# schematic_sheet2.net
KiCad netlist of a schematic drawn in Altium Designer
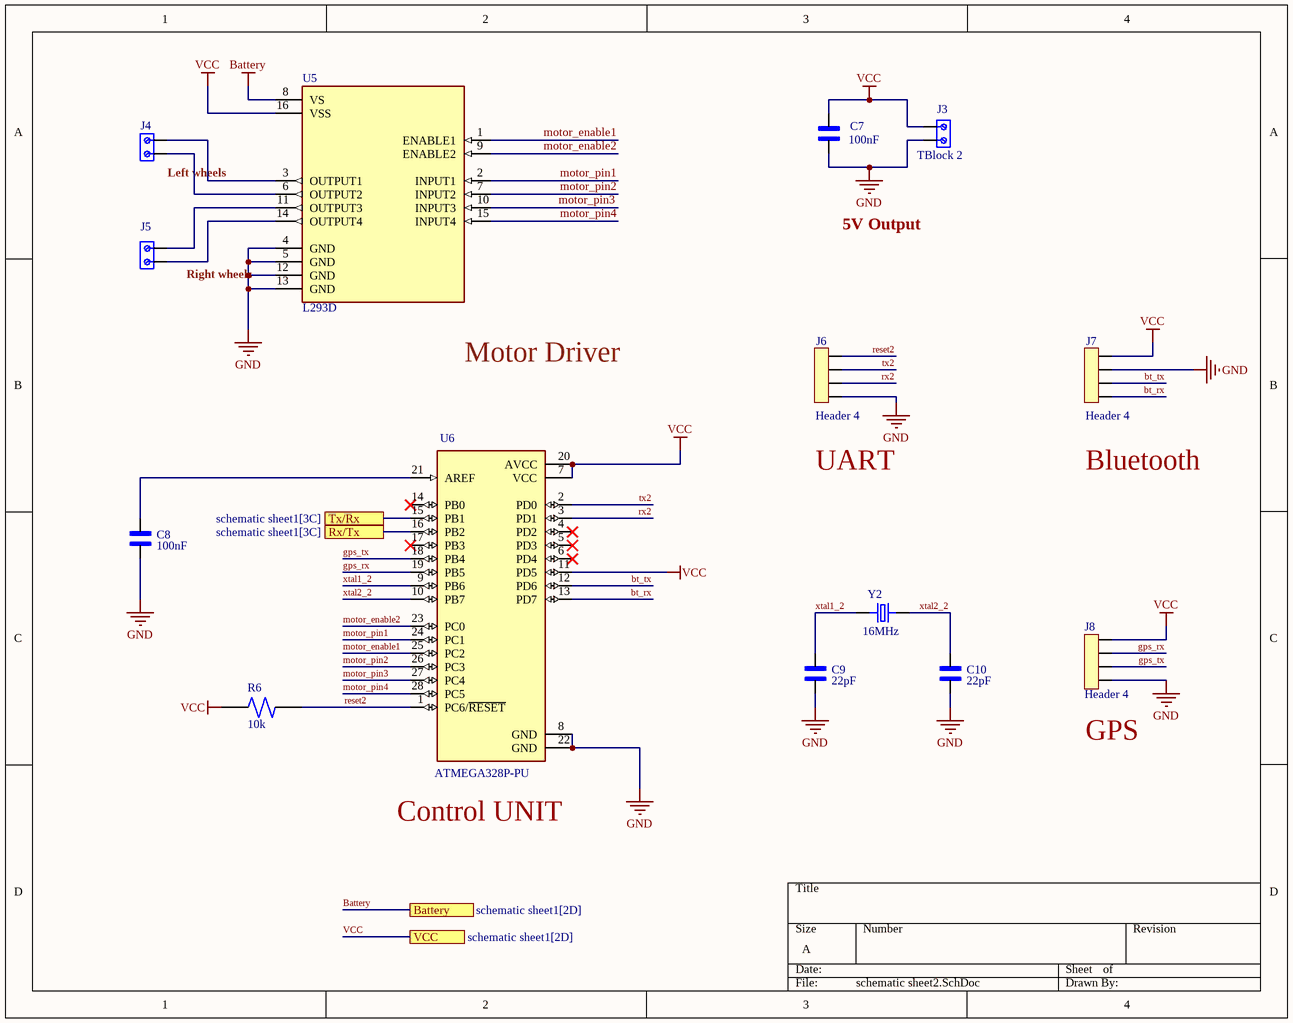
[diagram p0: schematic sheet2.SchDoc]

(export (version "E")
  (design (tool "Eeschema 10.0.6"))
  (components
    (comp (ref "C7")
      (value "100nF")
      (footprint "CAPRB500W50L450T300H550")
      (description "2200 pF Â±10% 250V Ceramic Capacitor X7R Radial")
      (fields (field (name "DIGI-KEY_PART_NUMBER") "445-173386-1-ND") (field (name "MF") "TDK"))
      (libsource (lib "") (part "Ceramic capacitor_1"))
    )
    (comp (ref "C8")
      (value "100nF")
      (footprint "CAPRB500W50L450T300H550")
      (description "2200 pF Â±10% 250V Ceramic Capacitor X7R Radial")
      (fields (field (name "DIGI-KEY_PART_NUMBER") "445-173386-1-ND") (field (name "MF") "TDK"))
      (libsource (lib "Installed library") (part "Ceramic capacitor"))
    )
    (comp (ref "C9")
      (value "22pF")
      (footprint "CAPRB500W50L450T300H550")
      (description "2200 pF Â±10% 250V Ceramic Capacitor X7R Radial")
      (fields (field (name "DIGI-KEY_PART_NUMBER") "445-173386-1-ND") (field (name "MF") "TDK"))
      (libsource (lib "Installed library") (part "Ceramic capacitor"))
    )
    (comp (ref "C10")
      (value "22pF")
      (footprint "CAPRB500W50L450T300H550")
      (description "2200 pF Â±10% 250V Ceramic Capacitor X7R Radial")
      (fields (field (name "DIGI-KEY_PART_NUMBER") "445-173386-1-ND") (field (name "MF") "TDK"))
      (libsource (lib "Installed library") (part "Ceramic capacitor"))
    )
    (comp (ref "J3")
      (value "TBlock 2")
      (footprint "691111710002")
      (description "2 Position Wire to Board Terminal Block Horizontal with Board 0.197 _5.00mm_ Through Hole")
      (fields (field (name "MP") "691111710002") (field (name "MF") "Wurth Electronics"))
      (libsource (lib "Installed library") (part "Terminal Block - 2Pins"))
    )
    (comp (ref "J4")
      (value "691111710002")
      (footprint "691111710002")
      (description "2 Position Wire to Board Terminal Block Horizontal with Board 0.197 _5.00mm_ Through Hole")
      (fields (field (name "MF") "Wurth Electronics"))
      (libsource (lib "Installed library") (part "Terminal Block - 2Pins"))
    )
    (comp (ref "J5")
      (value "691111710002")
      (footprint "691111710002")
      (description "2 Position Wire to Board Terminal Block Horizontal with Board 0.197 _5.00mm_ Through Hole")
      (fields (field (name "MF") "Wurth Electronics"))
      (libsource (lib "Installed library") (part "Terminal Block - 2Pins"))
    )
    (comp (ref "J6")
      (value "Header 4")
      (footprint "SULLINS_PPTC041LFBN-RC")
      (description "4 Position Header Connector Through Hole")
      (fields (field (name "MP") "PPTC041LFBN-RC") (field (name "MF") "Sullins Connector"))
      (libsource (lib "Installed library") (part "Female header - 4Pins"))
    )
    (comp (ref "J7")
      (value "Header 4")
      (footprint "SULLINS_PPTC041LFBN-RC")
      (description "4 Position Header Connector Through Hole")
      (fields (field (name "MP") "PPTC041LFBN-RC") (field (name "MF") "Sullins Connector"))
      (libsource (lib "Installed library") (part "Female header - 4Pins"))
    )
    (comp (ref "J8")
      (value "Header 4")
      (footprint "SULLINS_PPTC041LFBN-RC")
      (description "4 Position Header Connector Through Hole")
      (fields (field (name "MP") "PPTC041LFBN-RC") (field (name "MF") "Sullins Connector"))
      (libsource (lib "") (part "Female header - 4Pins_1"))
    )
    (comp (ref "R6")
      (value "10k")
      (footprint "RESAD1100W55L680D260")
      (description "(MFR-25FBF52-10K) 10,2 kOhm bei 1% 0,25W, 1/4W Durchbohrlochwiderstand Axial Metal Film")
      (fields (field (name "DIGI-KEY_PART_NUMBER") "10.2KXBK-ND") (field (name "MF") "Yageo"))
      (libsource (lib "Installed library") (part "Resistor (0.25W)"))
    )
    (comp (ref "U5")
      (value "L293D")
      (footprint "DIP880W50P254L2000H510Q16")
      (description "4-Channel Motor Driver 24V 16-Pin Power PDIP Tube")
      (libsource (lib "Installed library") (part "L293D"))
    )
    (comp (ref "U6")
      (value "ATMEGA328P-PU")
      (footprint "DIP794W46P254L2967H457Q28B")
      (description "ATmega Series 20 MHz 32 KB Flash 2 KB SRAM 8-Bit Microcontroller - DIP-28")
      (libsource (lib "Installed library") (part "ATMEGA328P-PU"))
    )
    (comp (ref "Y2")
      (value "16MHz")
      (footprint "XTAL_ECS-160-20-4X")
      (description "CRYSTAL T/H")
      (fields (field (name "MF") "{'manufacturer': u'ECS Inc.'}") (field (name "MP") "ECS-160-S-4"))
      (libsource (lib "Installed library") (part "Crystal oscilator"))
    )
  )
  (nets
    (net (code "1") (name "/Rx{slash}Tx") (class "Default")
      (node (ref "U6") (pin "16") (pinfunction "PB2_16") (pintype "bidirectional"))
    )
    (net (code "2") (name "/Tx{slash}Rx") (class "Default")
      (node (ref "U6") (pin "15") (pinfunction "PB1_15") (pintype "bidirectional"))
    )
    (net (code "3") (name "/bt_rx") (class "Default")
      (node (ref "J7") (pin "4") (pinfunction "4_4") (pintype "passive"))
      (node (ref "U6") (pin "13") (pinfunction "PD7_13") (pintype "bidirectional"))
    )
    (net (code "4") (name "/bt_tx") (class "Default")
      (node (ref "J7") (pin "3") (pinfunction "3_3") (pintype "passive"))
      (node (ref "U6") (pin "12") (pinfunction "PD6_12") (pintype "bidirectional"))
    )
    (net (code "5") (name "/gps_rx") (class "Default")
      (node (ref "J8") (pin "3") (pinfunction "3_3") (pintype "passive"))
      (node (ref "U6") (pin "19") (pinfunction "PB5_19") (pintype "bidirectional"))
    )
    (net (code "6") (name "/gps_tx") (class "Default")
      (node (ref "J8") (pin "2") (pinfunction "2_2") (pintype "passive"))
      (node (ref "U6") (pin "18") (pinfunction "PB4_18") (pintype "bidirectional"))
    )
    (net (code "7") (name "/motor_enable1") (class "Default")
      (node (ref "U5") (pin "1") (pinfunction "ENABLE1_1") (pintype "input"))
      (node (ref "U6") (pin "25") (pinfunction "PC2_25") (pintype "bidirectional"))
    )
    (net (code "8") (name "/motor_enable2") (class "Default")
      (node (ref "U5") (pin "9") (pinfunction "ENABLE2_9") (pintype "input"))
      (node (ref "U6") (pin "23") (pinfunction "PC0_23") (pintype "bidirectional"))
    )
    (net (code "9") (name "/motor_pin1") (class "Default")
      (node (ref "U5") (pin "2") (pinfunction "INPUT1_2") (pintype "input"))
      (node (ref "U6") (pin "24") (pinfunction "PC1_24") (pintype "bidirectional"))
    )
    (net (code "10") (name "/motor_pin2") (class "Default")
      (node (ref "U5") (pin "7") (pinfunction "INPUT2_7") (pintype "input"))
      (node (ref "U6") (pin "26") (pinfunction "PC3_26") (pintype "bidirectional"))
    )
    (net (code "11") (name "/motor_pin3") (class "Default")
      (node (ref "U5") (pin "10") (pinfunction "INPUT3_10") (pintype "input"))
      (node (ref "U6") (pin "27") (pinfunction "PC4_27") (pintype "bidirectional"))
    )
    (net (code "12") (name "/motor_pin4") (class "Default")
      (node (ref "U5") (pin "15") (pinfunction "INPUT4_15") (pintype "input"))
      (node (ref "U6") (pin "28") (pinfunction "PC5_28") (pintype "bidirectional"))
    )
    (net (code "13") (name "/reset2") (class "Default")
      (node (ref "J6") (pin "1") (pinfunction "1_1") (pintype "passive"))
      (node (ref "R6") (pin "2") (pinfunction "2_2") (pintype "passive"))
      (node (ref "U6") (pin "1") (pinfunction "PC6/~{RESET}_1") (pintype "bidirectional"))
    )
    (net (code "14") (name "/rx2") (class "Default")
      (node (ref "J6") (pin "3") (pinfunction "3_3") (pintype "passive"))
      (node (ref "U6") (pin "3") (pinfunction "PD1_3") (pintype "bidirectional"))
    )
    (net (code "15") (name "/tx2") (class "Default")
      (node (ref "J6") (pin "2") (pinfunction "2_2") (pintype "passive"))
      (node (ref "U6") (pin "2") (pinfunction "PD0_2") (pintype "bidirectional"))
    )
    (net (code "16") (name "/xtal1_2") (class "Default")
      (node (ref "C9") (pin "1") (pinfunction "1_1") (pintype "passive"))
      (node (ref "U6") (pin "9") (pinfunction "PB6_9") (pintype "bidirectional"))
      (node (ref "Y2") (pin "1") (pinfunction "1_1") (pintype "passive"))
    )
    (net (code "17") (name "/xtal2_2") (class "Default")
      (node (ref "C10") (pin "1") (pinfunction "1_1") (pintype "passive"))
      (node (ref "U6") (pin "10") (pinfunction "PB7_10") (pintype "bidirectional"))
      (node (ref "Y2") (pin "2") (pinfunction "2_2") (pintype "passive"))
    )
    (net (code "18") (name "Battery") (class "Default")
      (node (ref "U5") (pin "8") (pinfunction "VS_8") (pintype "power_in"))
    )
    (net (code "19") (name "GND") (class "Default")
      (node (ref "C10") (pin "2") (pinfunction "2_2") (pintype "passive"))
      (node (ref "C7") (pin "1") (pinfunction "1_1") (pintype "passive"))
      (node (ref "C8") (pin "2") (pinfunction "2_2") (pintype "passive"))
      (node (ref "C9") (pin "2") (pinfunction "2_2") (pintype "passive"))
      (node (ref "J3") (pin "2") (pinfunction "2_2") (pintype "passive"))
      (node (ref "J6") (pin "4") (pinfunction "4_4") (pintype "passive"))
      (node (ref "J7") (pin "2") (pinfunction "2_2") (pintype "passive"))
      (node (ref "J8") (pin "1") (pinfunction "1_1") (pintype "passive"))
      (node (ref "U5") (pin "12") (pinfunction "GND_12") (pintype "power_in"))
      (node (ref "U5") (pin "13") (pinfunction "GND_13") (pintype "power_in"))
      (node (ref "U5") (pin "4") (pinfunction "GND_4") (pintype "power_in"))
      (node (ref "U5") (pin "5") (pinfunction "GND_5") (pintype "power_in"))
      (node (ref "U6") (pin "22") (pinfunction "GND_22") (pintype "power_in"))
      (node (ref "U6") (pin "8") (pinfunction "GND_8") (pintype "power_in"))
    )
    (net (code "20") (name "Net-(U5-OUTPUT1)") (class "Default")
      (node (ref "J4") (pin "1") (pinfunction "1_1") (pintype "passive"))
      (node (ref "U5") (pin "3") (pinfunction "OUTPUT1_3") (pintype "output"))
    )
    (net (code "21") (name "Net-(U5-OUTPUT2)") (class "Default")
      (node (ref "J4") (pin "2") (pinfunction "2_2") (pintype "passive"))
      (node (ref "U5") (pin "6") (pinfunction "OUTPUT2_6") (pintype "output"))
    )
    (net (code "22") (name "Net-(U5-OUTPUT3)") (class "Default")
      (node (ref "J5") (pin "1") (pinfunction "1_1") (pintype "passive"))
      (node (ref "U5") (pin "11") (pinfunction "OUTPUT3_11") (pintype "output"))
    )
    (net (code "23") (name "Net-(U5-OUTPUT4)") (class "Default")
      (node (ref "J5") (pin "2") (pinfunction "2_2") (pintype "passive"))
      (node (ref "U5") (pin "14") (pinfunction "OUTPUT4_14") (pintype "output"))
    )
    (net (code "24") (name "Net-(U6-AREF)") (class "Default")
      (node (ref "C8") (pin "1") (pinfunction "1_1") (pintype "passive"))
      (node (ref "U6") (pin "21") (pinfunction "AREF_21") (pintype "input"))
    )
    (net (code "25") (name "VCC") (class "Default")
      (node (ref "C7") (pin "2") (pinfunction "2_2") (pintype "passive"))
      (node (ref "J3") (pin "1") (pinfunction "1_1") (pintype "passive"))
      (node (ref "J7") (pin "1") (pinfunction "1_1") (pintype "passive"))
      (node (ref "J8") (pin "4") (pinfunction "4_4") (pintype "passive"))
      (node (ref "R6") (pin "1") (pinfunction "1_1") (pintype "passive"))
      (node (ref "U5") (pin "16") (pinfunction "VSS_16") (pintype "power_in"))
      (node (ref "U6") (pin "11") (pinfunction "PD5_11") (pintype "bidirectional"))
      (node (ref "U6") (pin "20") (pinfunction "AVCC_20") (pintype "power_in"))
      (node (ref "U6") (pin "7") (pinfunction "VCC_7") (pintype "power_in"))
    )
    (net (code "26") (name "unconnected-(U6-PB0-Pad14)") (class "Default")
      (node (ref "U6") (pin "14") (pinfunction "PB0_14") (pintype "bidirectional+no_connect"))
    )
    (net (code "27") (name "unconnected-(U6-PB3-Pad17)") (class "Default")
      (node (ref "U6") (pin "17") (pinfunction "PB3_17") (pintype "bidirectional+no_connect"))
    )
    (net (code "28") (name "unconnected-(U6-PD2-Pad4)") (class "Default")
      (node (ref "U6") (pin "4") (pinfunction "PD2_4") (pintype "bidirectional+no_connect"))
    )
    (net (code "29") (name "unconnected-(U6-PD3-Pad5)") (class "Default")
      (node (ref "U6") (pin "5") (pinfunction "PD3_5") (pintype "bidirectional+no_connect"))
    )
    (net (code "30") (name "unconnected-(U6-PD4-Pad6)") (class "Default")
      (node (ref "U6") (pin "6") (pinfunction "PD4_6") (pintype "bidirectional+no_connect"))
    )
  )
)
